# STM32_for_Cal_V1_0.net
KiCad netlist of a schematic drawn in Altium Designer
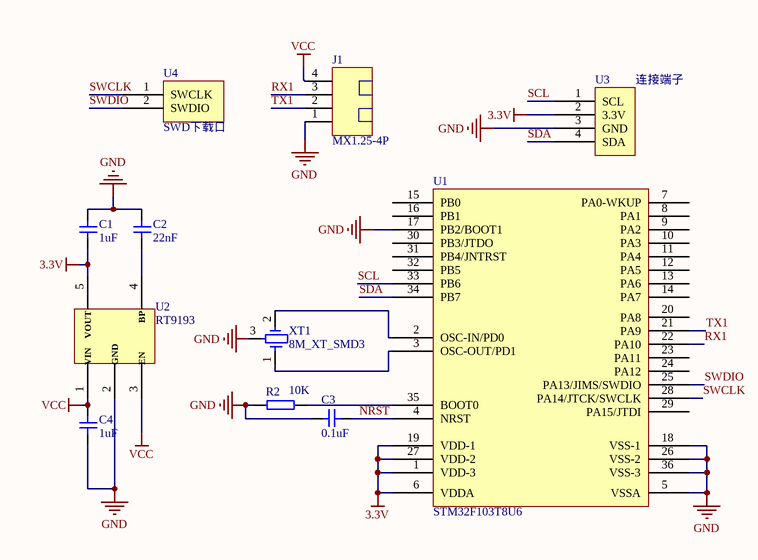
[diagram p0: STM32 for Cal V1.0.SchDoc]

(export (version "E")
  (design (tool "Eeschema 10.0.6"))
  (components
    (comp (ref "C1")
      (value "1uF")
      (footprint "0603C")
      (description "无极贴片电容")
      (libsource (lib "My ku") (part "Cap1"))
    )
    (comp (ref "C2")
      (value "22nF")
      (footprint "0603C")
      (description "无极贴片电容")
      (libsource (lib "My ku") (part "Cap1"))
    )
    (comp (ref "C3")
      (value "0.1uF")
      (footprint "0603C")
      (description "无极贴片电容")
      (libsource (lib "集大电协1.1.5") (part "Cap1"))
    )
    (comp (ref "C4")
      (value "1uF")
      (footprint "0603C")
      (description "无极贴片电容")
      (libsource (lib "集大电协1.1.5") (part "Cap1"))
    )
    (comp (ref "J1")
      (value "MX1.25-4P")
      (footprint "MX1.25-4P")
      (libsource (lib "Schlib1") (part "MX1.25-4P_1"))
    )
    (comp (ref "R2")
      (value "10K")
      (footprint "0603R")
      (description "电阻")
      (libsource (lib "集大电协1.1.5") (part "Res"))
    )
    (comp (ref "U1")
      (value "STM32F103T8U6")
      (footprint "QFN-36B6R00x6R00")
      (libsource (lib "集大电协1.1.5") (part "STM32F103T8U6"))
    )
    (comp (ref "U2") (value "RT9193") (footprint "RT9193") (libsource (lib "Schlib1") (part "RT9193")))
    (comp (ref "U3") (value "连接端子") (footprint "连接端子") (libsource (lib "集大电协1.1.5") (part "连接端子")))
    (comp (ref "U4") (value "SWD下载口") (footprint "SWD下载口") (libsource (lib "集大电协1.5(1)") (part "SWD下载口")))
    (comp (ref "XT1")
      (value "8M_XT_SMD3")
      (footprint "三脚贴片8M晶振1.5*3.5")
      (libsource (lib "集大电协1.1.5") (part "8M_XT-SMD3"))
    )
  )
  (nets
    (net (code "1") (name "/NRST") (class "Default")
      (node (ref "C3") (pin "1") (pinfunction "1_1") (pintype "passive"))
      (node (ref "U1") (pin "4") (pinfunction "NRST_4") (pintype "passive"))
    )
    (net (code "2") (name "/RX1") (class "Default")
      (node (ref "J1") (pin "3") (pinfunction "3_3") (pintype "passive"))
      (node (ref "U1") (pin "22") (pinfunction "PA10_22") (pintype "passive"))
    )
    (net (code "3") (name "/SCL") (class "Default")
      (node (ref "U1") (pin "33") (pinfunction "PB6_33") (pintype "passive"))
      (node (ref "U3") (pin "1") (pinfunction "SCL_1") (pintype "passive"))
    )
    (net (code "4") (name "/SDA") (class "Default")
      (node (ref "U1") (pin "34") (pinfunction "PB7_34") (pintype "passive"))
      (node (ref "U3") (pin "4") (pinfunction "SDA_4") (pintype "passive"))
    )
    (net (code "5") (name "/SWCLK") (class "Default")
      (node (ref "U1") (pin "28") (pinfunction "PA14/JTCK/SWCLK_28") (pintype "passive"))
      (node (ref "U4") (pin "1") (pinfunction "SWCLK_1") (pintype "passive"))
    )
    (net (code "6") (name "/SWDIO") (class "Default")
      (node (ref "U1") (pin "25") (pinfunction "PA13/JIMS/SWDIO_25") (pintype "passive"))
      (node (ref "U4") (pin "2") (pinfunction "SWDIO_2") (pintype "passive"))
    )
    (net (code "7") (name "/TX1") (class "Default")
      (node (ref "J1") (pin "2") (pinfunction "2_2") (pintype "passive"))
      (node (ref "U1") (pin "21") (pinfunction "PA9_21") (pintype "passive"))
    )
    (net (code "8") (name "3.3V") (class "Default")
      (node (ref "C1") (pin "1") (pinfunction "1_1") (pintype "passive"))
      (node (ref "U1") (pin "1") (pinfunction "VDD-3_1") (pintype "passive"))
      (node (ref "U1") (pin "19") (pinfunction "VDD-1_19") (pintype "passive"))
      (node (ref "U1") (pin "27") (pinfunction "VDD-2_27") (pintype "passive"))
      (node (ref "U1") (pin "6") (pinfunction "VDDA_6") (pintype "passive"))
      (node (ref "U2") (pin "5") (pinfunction "VOUT_5") (pintype "passive"))
      (node (ref "U3") (pin "2") (pinfunction "3.3V_2") (pintype "passive"))
    )
    (net (code "9") (name "GND") (class "Default")
      (node (ref "C1") (pin "2") (pinfunction "2_2") (pintype "passive"))
      (node (ref "C2") (pin "2") (pinfunction "2_2") (pintype "passive"))
      (node (ref "C3") (pin "2") (pinfunction "2_2") (pintype "passive"))
      (node (ref "C4") (pin "1") (pinfunction "1_1") (pintype "passive"))
      (node (ref "J1") (pin "1") (pinfunction "1_1") (pintype "passive"))
      (node (ref "R2") (pin "1") (pinfunction "1_1") (pintype "passive"))
      (node (ref "U1") (pin "17") (pinfunction "PB2/BOOT1_17") (pintype "passive"))
      (node (ref "U1") (pin "18") (pinfunction "VSS-1_18") (pintype "passive"))
      (node (ref "U1") (pin "26") (pinfunction "VSS-2_26") (pintype "passive"))
      (node (ref "U1") (pin "36") (pinfunction "VSS-3_36") (pintype "passive"))
      (node (ref "U1") (pin "5") (pinfunction "VSSA_5") (pintype "passive"))
      (node (ref "U2") (pin "2") (pinfunction "GND_2") (pintype "passive"))
      (node (ref "U3") (pin "3") (pinfunction "GND_3") (pintype "passive"))
      (node (ref "XT1") (pin "3") (pinfunction "3_3") (pintype "passive"))
    )
    (net (code "10") (name "Net-(U1-BOOT0)") (class "Default")
      (node (ref "R2") (pin "2") (pinfunction "2_2") (pintype "passive"))
      (node (ref "U1") (pin "35") (pinfunction "BOOT0_35") (pintype "passive"))
    )
    (net (code "11") (name "Net-(U1-OSC-IN{slash}PD0)") (class "Default")
      (node (ref "U1") (pin "2") (pinfunction "OSC-IN/PD0_2") (pintype "passive"))
      (node (ref "XT1") (pin "2") (pinfunction "2_2") (pintype "passive"))
    )
    (net (code "12") (name "Net-(U1-OSC-OUT{slash}PD1)") (class "Default")
      (node (ref "U1") (pin "3") (pinfunction "OSC-OUT/PD1_3") (pintype "passive"))
      (node (ref "XT1") (pin "1") (pinfunction "1_1") (pintype "passive"))
    )
    (net (code "13") (name "Net-(U2-BP)") (class "Default")
      (node (ref "C2") (pin "1") (pinfunction "1_1") (pintype "passive"))
      (node (ref "U2") (pin "4") (pinfunction "BP_4") (pintype "passive"))
    )
    (net (code "14") (name "VCC") (class "Default")
      (node (ref "C4") (pin "2") (pinfunction "2_2") (pintype "passive"))
      (node (ref "J1") (pin "4") (pinfunction "4_4") (pintype "passive"))
      (node (ref "U2") (pin "1") (pinfunction "VIN_1") (pintype "passive"))
      (node (ref "U2") (pin "3") (pinfunction "EN_3") (pintype "passive"))
    )
    (net (code "15") (name "unconnected-(U1-PA0-WKUP-Pad7)") (class "Default")
      (node (ref "U1") (pin "7") (pinfunction "PA0-WKUP_7") (pintype "passive"))
    )
    (net (code "16") (name "unconnected-(U1-PA1-Pad8)") (class "Default")
      (node (ref "U1") (pin "8") (pinfunction "PA1_8") (pintype "passive"))
    )
    (net (code "17") (name "unconnected-(U1-PA2-Pad9)") (class "Default")
      (node (ref "U1") (pin "9") (pinfunction "PA2_9") (pintype "passive"))
    )
    (net (code "18") (name "unconnected-(U1-PA3-Pad10)") (class "Default")
      (node (ref "U1") (pin "10") (pinfunction "PA3_10") (pintype "passive"))
    )
    (net (code "19") (name "unconnected-(U1-PA4-Pad11)") (class "Default")
      (node (ref "U1") (pin "11") (pinfunction "PA4_11") (pintype "passive"))
    )
    (net (code "20") (name "unconnected-(U1-PA5-Pad12)") (class "Default")
      (node (ref "U1") (pin "12") (pinfunction "PA5_12") (pintype "passive"))
    )
    (net (code "21") (name "unconnected-(U1-PA6-Pad13)") (class "Default")
      (node (ref "U1") (pin "13") (pinfunction "PA6_13") (pintype "passive"))
    )
    (net (code "22") (name "unconnected-(U1-PA7-Pad14)") (class "Default")
      (node (ref "U1") (pin "14") (pinfunction "PA7_14") (pintype "passive"))
    )
    (net (code "23") (name "unconnected-(U1-PA8-Pad20)") (class "Default")
      (node (ref "U1") (pin "20") (pinfunction "PA8_20") (pintype "passive"))
    )
    (net (code "24") (name "unconnected-(U1-PA11-Pad23)") (class "Default")
      (node (ref "U1") (pin "23") (pinfunction "PA11_23") (pintype "passive"))
    )
    (net (code "25") (name "unconnected-(U1-PA12-Pad24)") (class "Default")
      (node (ref "U1") (pin "24") (pinfunction "PA12_24") (pintype "passive"))
    )
    (net (code "26") (name "unconnected-(U1-PA15{slash}JTDI-Pad29)") (class "Default")
      (node (ref "U1") (pin "29") (pinfunction "PA15/JTDI_29") (pintype "passive"))
    )
    (net (code "27") (name "unconnected-(U1-PB0-Pad15)") (class "Default")
      (node (ref "U1") (pin "15") (pinfunction "PB0_15") (pintype "passive"))
    )
    (net (code "28") (name "unconnected-(U1-PB1-Pad16)") (class "Default")
      (node (ref "U1") (pin "16") (pinfunction "PB1_16") (pintype "passive"))
    )
    (net (code "29") (name "unconnected-(U1-PB3{slash}JTDO-Pad30)") (class "Default")
      (node (ref "U1") (pin "30") (pinfunction "PB3/JTDO_30") (pintype "passive"))
    )
    (net (code "30") (name "unconnected-(U1-PB4{slash}JNTRST-Pad31)") (class "Default")
      (node (ref "U1") (pin "31") (pinfunction "PB4/JNTRST_31") (pintype "passive"))
    )
    (net (code "31") (name "unconnected-(U1-PB5-Pad32)") (class "Default")
      (node (ref "U1") (pin "32") (pinfunction "PB5_32") (pintype "passive"))
    )
  )
)
